# 2DBarcodeScanner.net
KiCad netlist of a schematic drawn in EAGLE
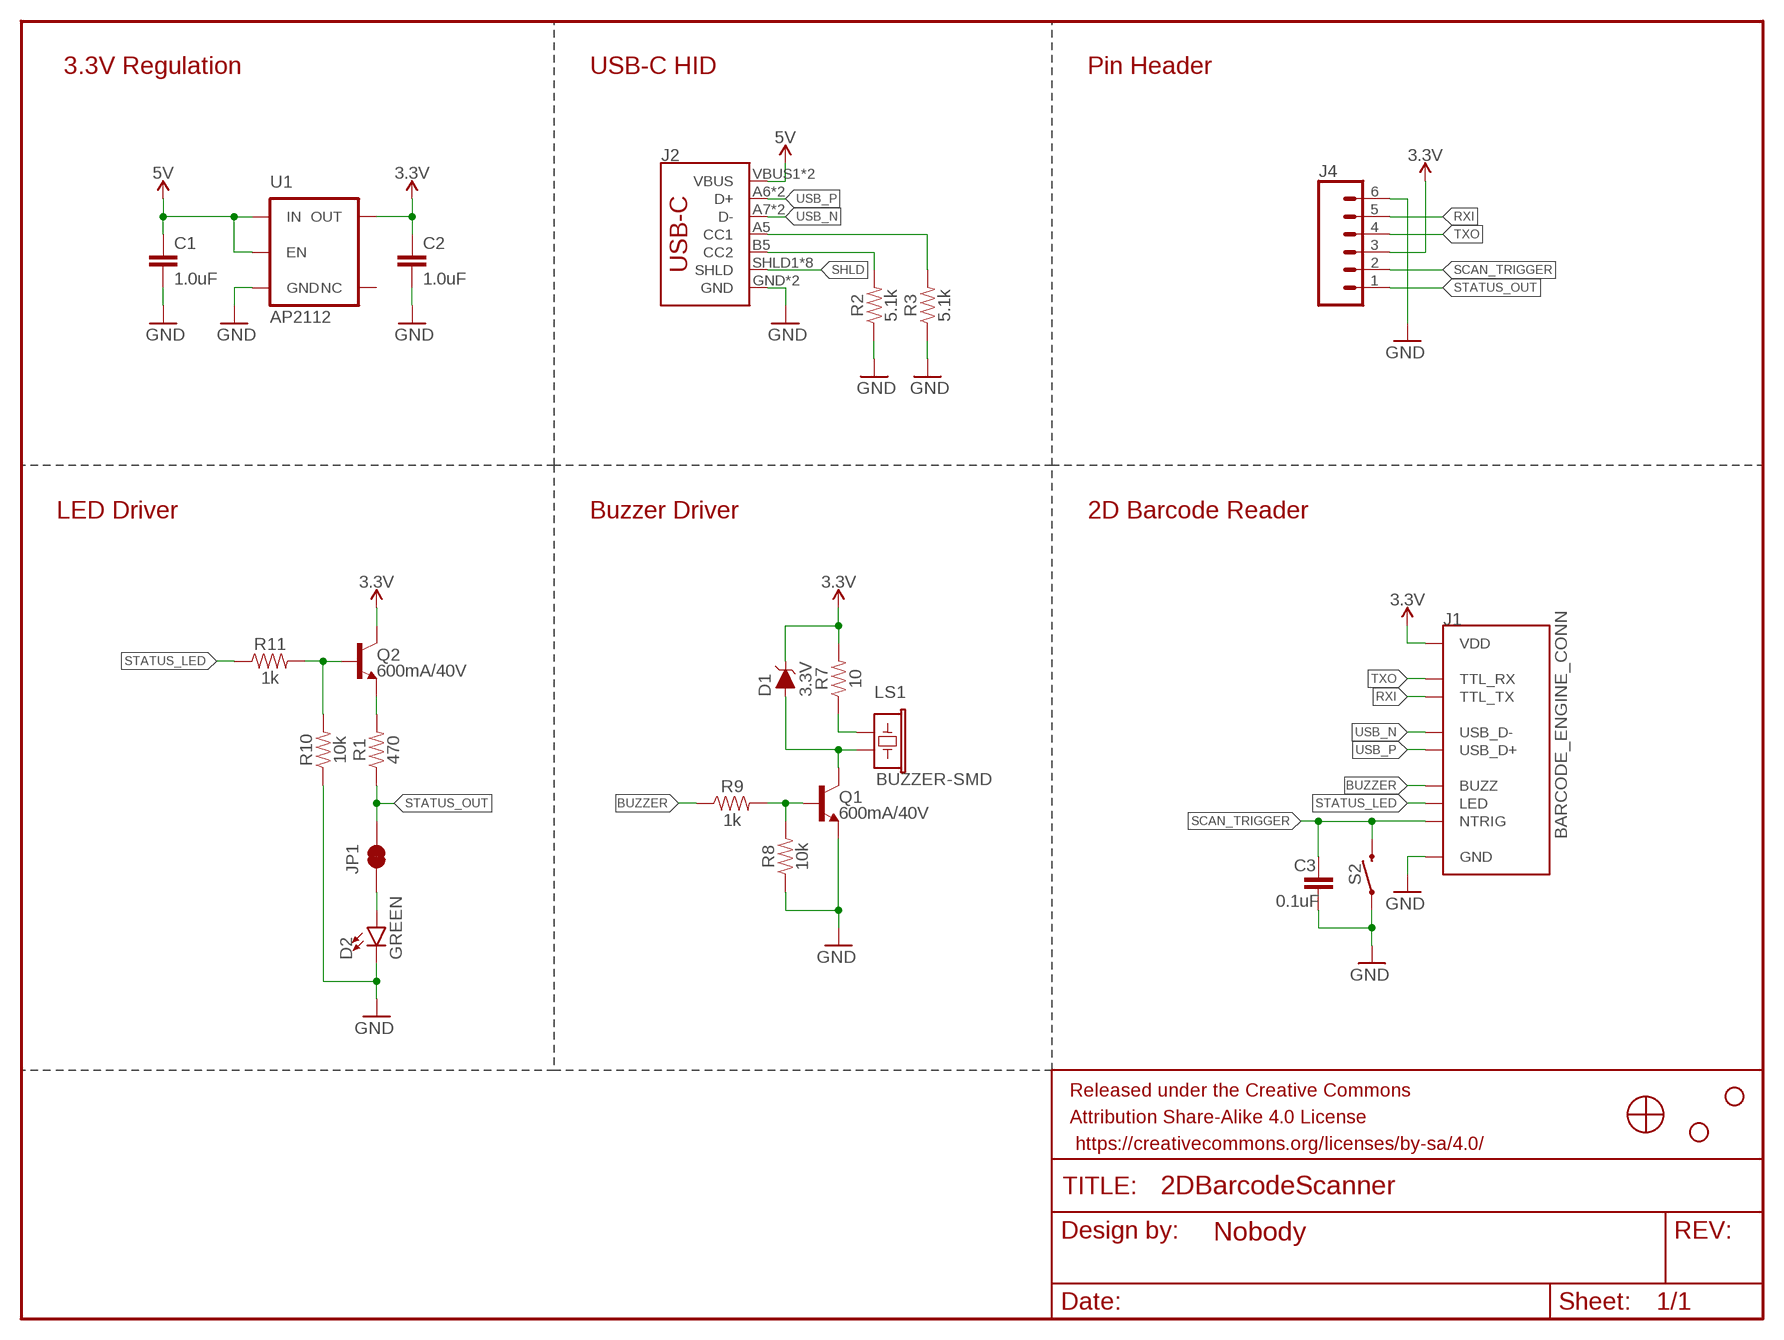
[diagram p0: schematic, sheet 1]

(export (version "E")
  (design (tool "Eeschema 10.0.6"))
  (components
    (comp (ref "C1")
      (value "1.0uF")
      (footprint "eagle-import:0603")
      (libsource (lib "eagle-import") (part "1.0UF-0603-16V-10%"))
    )
    (comp (ref "C2")
      (value "1.0uF")
      (footprint "eagle-import:0603")
      (libsource (lib "eagle-import") (part "1.0UF-0603-16V-10%"))
    )
    (comp (ref "C3")
      (value "0.1uF")
      (footprint "eagle-import:0603")
      (libsource (lib "eagle-import") (part "0.1UF-0603-25V-(+80/-20%)"))
    )
    (comp (ref "D1")
      (value "3.3V")
      (footprint "eagle-import:SOD-323")
      (libsource (lib "eagle-import") (part "DIODE-ZENER-MM3Z3V3T1G"))
    )
    (comp (ref "D2")
      (value "GREEN")
      (footprint "eagle-import:LED-0603")
      (libsource (lib "eagle-import") (part "LED-GREEN0603"))
    )
    (comp (ref "FRAME1")
      (value "FRAME-LETTERNO_PACKAGE")
      (footprint "eagle-import:DUMMY")
      (fields (field (name "DESIGNER") "Nobody"))
      (libsource (lib "eagle-import") (part "FRAME-LETTERNO_PACKAGE"))
    )
    (comp (ref "H2")
      (value "STAND-OFF")
      (footprint "eagle-import:STAND-OFF")
      (libsource (lib "eagle-import") (part "STAND-OFF"))
    )
    (comp (ref "H3")
      (value "STAND-OFF")
      (footprint "eagle-import:STAND-OFF")
      (libsource (lib "eagle-import") (part "STAND-OFF"))
    )
    (comp (ref "J1")
      (value "BARCODE_ENGINE_CONN")
      (footprint "eagle-import:CONN_FPC_BOTTOM_12POS_.5MM_R_A")
      (libsource (lib "eagle-import") (part "BARCODE_ENGINE_CONN"))
    )
    (comp (ref "J2")
      (value "USB_C2-LAYER")
      (footprint "eagle-import:USB-C-16P")
      (libsource (lib "eagle-import") (part "USB_C2-LAYER"))
    )
    (comp (ref "J4")
      (value "CONN_06NO_SILK_FEMALE_PTH")
      (footprint "eagle-import:1X06_NO_SILK")
      (libsource (lib "eagle-import") (part "CONN_06NO_SILK_FEMALE_PTH"))
    )
    (comp (ref "JP1")
      (value "JUMPER-SMT_2_NC_TRACE_SILK")
      (footprint "eagle-import:SMT-JUMPER_2_NC_TRACE_SILK")
      (libsource (lib "eagle-import") (part "JUMPER-SMT_2_NC_TRACE_SILK"))
    )
    (comp (ref "LS1")
      (value "BUZZER-SMD")
      (footprint "eagle-import:BUZZER-CCV")
      (libsource (lib "eagle-import") (part "BUZZER-SMD"))
    )
    (comp (ref "Q1")
      (value "600mA/40V")
      (footprint "eagle-import:SOT23-3")
      (libsource (lib "eagle-import") (part "TRANS_NPN-MMBT2222AL"))
    )
    (comp (ref "Q2")
      (value "600mA/40V")
      (footprint "eagle-import:SOT23-3")
      (libsource (lib "eagle-import") (part "TRANS_NPN-MMBT2222AL"))
    )
    (comp (ref "R1")
      (value "470")
      (footprint "eagle-import:0603")
      (libsource (lib "eagle-import") (part "470OHM-0603-1/10W-1%"))
    )
    (comp (ref "R2")
      (value "5.1k")
      (footprint "eagle-import:0603")
      (libsource (lib "eagle-import") (part "5.1KOHM5.1KOHM-0603-1/10W-1%"))
    )
    (comp (ref "R3")
      (value "5.1k")
      (footprint "eagle-import:0603")
      (libsource (lib "eagle-import") (part "5.1KOHM5.1KOHM-0603-1/10W-1%"))
    )
    (comp (ref "R7")
      (value "10")
      (footprint "eagle-import:0603")
      (libsource (lib "eagle-import") (part "10OHM-0603-1/10W-5%"))
    )
    (comp (ref "R8")
      (value "10k")
      (footprint "eagle-import:0603")
      (libsource (lib "eagle-import") (part "10KOHM-0603-1/10W-1%"))
    )
    (comp (ref "R9")
      (value "1k")
      (footprint "eagle-import:0603")
      (libsource (lib "eagle-import") (part "1KOHM-0603-1/10W-1%"))
    )
    (comp (ref "R10")
      (value "10k")
      (footprint "eagle-import:0603")
      (libsource (lib "eagle-import") (part "10KOHM-0603-1/10W-1%"))
    )
    (comp (ref "R11")
      (value "1k")
      (footprint "eagle-import:0603")
      (libsource (lib "eagle-import") (part "1KOHM-0603-1/10W-1%"))
    )
    (comp (ref "S2")
      (value "MOMENTARY-SWITCH-SPST-SMD-5.2MM-TALL")
      (footprint "eagle-import:TACTILE_SWITCH_SMD_5.2MM")
      (libsource (lib "eagle-import") (part "MOMENTARY-SWITCH-SPST-SMD-5.2MM-TALL"))
    )
    (comp (ref "U$1")
      (value "BARCODE_SCANNER_MOUNT")
      (footprint "eagle-import:BARCODE_SCANNER_MOUNT")
      (libsource (lib "eagle-import") (part "BARCODE_SCANNER_MOUNT"))
    )
    (comp (ref "U1")
      (value "3.3V")
      (footprint "eagle-import:SOT23-5")
      (libsource (lib "eagle-import") (part "V_REG_AP2112K-3.3V"))
    )
  )
  (nets
    (net (code "1") (name "3.3V") (class "Default")
      (node (ref "C2") (pin "1") (pinfunction "1_1") (pintype "passive"))
      (node (ref "D1") (pin "C") (pinfunction "C_C") (pintype "passive"))
      (node (ref "J1") (pin "P$11") (pinfunction "VDD_P$11") (pintype "power_in"))
      (node (ref "J4") (pin "3") (pinfunction "3_3") (pintype "passive"))
      (node (ref "Q2") (pin "3") (pinfunction "C_3") (pintype "passive"))
      (node (ref "R7") (pin "2") (pinfunction "2_2") (pintype "passive"))
      (node (ref "U1") (pin "5") (pinfunction "OUT_5") (pintype "passive"))
    )
    (net (code "2") (name "5V") (class "Default")
      (node (ref "C1") (pin "1") (pinfunction "1_1") (pintype "passive"))
      (node (ref "J2") (pin "VBUS1") (pinfunction "VBUS_VBUS1") (pintype "bidirectional"))
      (node (ref "J2") (pin "VBUS2") (pinfunction "VBUS_VBUS2") (pintype "bidirectional"))
      (node (ref "U1") (pin "1") (pinfunction "IN_1") (pintype "input"))
      (node (ref "U1") (pin "3") (pinfunction "EN_3") (pintype "input"))
    )
    (net (code "3") (name "BUZZER") (class "Default")
      (node (ref "J1") (pin "P$4") (pinfunction "BUZZ_P$4") (pintype "output"))
      (node (ref "R9") (pin "1") (pinfunction "1_1") (pintype "passive"))
    )
    (net (code "4") (name "GND") (class "Default")
      (node (ref "C1") (pin "2") (pinfunction "2_2") (pintype "passive"))
      (node (ref "C2") (pin "2") (pinfunction "2_2") (pintype "passive"))
      (node (ref "C3") (pin "2") (pinfunction "2_2") (pintype "passive"))
      (node (ref "D2") (pin "C") (pinfunction "C_C") (pintype "passive"))
      (node (ref "J1") (pin "P$10") (pinfunction "GND_P$10") (pintype "power_in"))
      (node (ref "J1") (pin "P$13") (pinfunction "GND_P$13") (pintype "power_in"))
      (node (ref "J1") (pin "P$14") (pinfunction "GND_P$14") (pintype "power_in"))
      (node (ref "J2") (pin "GND") (pinfunction "GND_GND") (pintype "bidirectional"))
      (node (ref "J2") (pin "GND2") (pinfunction "GND_GND2") (pintype "bidirectional"))
      (node (ref "J4") (pin "6") (pinfunction "6_6") (pintype "passive"))
      (node (ref "Q1") (pin "2") (pinfunction "E_2") (pintype "passive"))
      (node (ref "R10") (pin "1") (pinfunction "1_1") (pintype "passive"))
      (node (ref "R2") (pin "1") (pinfunction "1_1") (pintype "passive"))
      (node (ref "R3") (pin "1") (pinfunction "1_1") (pintype "passive"))
      (node (ref "R8") (pin "1") (pinfunction "1_1") (pintype "passive"))
      (node (ref "S2") (pin "1") (pinfunction "1_1") (pintype "passive"))
      (node (ref "U1") (pin "2") (pinfunction "GND_2") (pintype "input"))
    )
    (net (code "5") (name "Net-(D2-PadA)") (class "Default")
      (node (ref "D2") (pin "A") (pinfunction "A_A") (pintype "passive"))
      (node (ref "JP1") (pin "1") (pinfunction "1_1") (pintype "passive"))
    )
    (net (code "6") (name "Net-(J2-CC1)") (class "Default")
      (node (ref "J2") (pin "A5") (pinfunction "CC1_A5") (pintype "bidirectional"))
      (node (ref "R3") (pin "2") (pinfunction "2_2") (pintype "passive"))
    )
    (net (code "7") (name "Net-(J2-CC2)") (class "Default")
      (node (ref "J2") (pin "B5") (pinfunction "CC2_B5") (pintype "bidirectional"))
      (node (ref "R2") (pin "2") (pinfunction "2_2") (pintype "passive"))
    )
    (net (code "8") (name "Net-(LS1-1)") (class "Default")
      (node (ref "LS1") (pin "+") (pinfunction "1_+") (pintype "passive"))
      (node (ref "R7") (pin "1") (pinfunction "1_1") (pintype "passive"))
    )
    (net (code "9") (name "Net-(LS1-2)") (class "Default")
      (node (ref "D1") (pin "A") (pinfunction "A_A") (pintype "passive"))
      (node (ref "LS1") (pin "-") (pinfunction "2_-") (pintype "passive"))
      (node (ref "Q1") (pin "3") (pinfunction "C_3") (pintype "passive"))
    )
    (net (code "10") (name "Net-(Q1-B)") (class "Default")
      (node (ref "Q1") (pin "1") (pinfunction "B_1") (pintype "passive"))
      (node (ref "R8") (pin "2") (pinfunction "2_2") (pintype "passive"))
      (node (ref "R9") (pin "2") (pinfunction "2_2") (pintype "passive"))
    )
    (net (code "11") (name "Net-(Q2-B)") (class "Default")
      (node (ref "Q2") (pin "1") (pinfunction "B_1") (pintype "passive"))
      (node (ref "R10") (pin "2") (pinfunction "2_2") (pintype "passive"))
      (node (ref "R11") (pin "2") (pinfunction "2_2") (pintype "passive"))
    )
    (net (code "12") (name "Net-(Q2-E)") (class "Default")
      (node (ref "Q2") (pin "2") (pinfunction "E_2") (pintype "passive"))
      (node (ref "R1") (pin "2") (pinfunction "2_2") (pintype "passive"))
    )
    (net (code "13") (name "RXI") (class "Default")
      (node (ref "J1") (pin "P$8") (pinfunction "TTL_TX_P$8") (pintype "output"))
      (node (ref "J4") (pin "5") (pinfunction "5_5") (pintype "passive"))
    )
    (net (code "14") (name "SCAN_TRIGGER") (class "Default")
      (node (ref "C3") (pin "1") (pinfunction "1_1") (pintype "passive"))
      (node (ref "J1") (pin "P$1") (pinfunction "NTRIG_P$1") (pintype "input"))
      (node (ref "J4") (pin "2") (pinfunction "2_2") (pintype "passive"))
      (node (ref "S2") (pin "3") (pinfunction "2_3") (pintype "passive"))
    )
    (net (code "15") (name "SHLD") (class "Default")
      (node (ref "J2") (pin "SHLD1") (pinfunction "SHLD_SHLD1") (pintype "bidirectional"))
      (node (ref "J2") (pin "SHLD2") (pinfunction "SHLD_SHLD2") (pintype "bidirectional"))
      (node (ref "J2") (pin "SHLD3") (pinfunction "SHLD_SHLD3") (pintype "bidirectional"))
      (node (ref "J2") (pin "SHLD4") (pinfunction "SHLD_SHLD4") (pintype "bidirectional"))
      (node (ref "J2") (pin "SHLD5") (pinfunction "SHLD_SHLD5") (pintype "bidirectional"))
      (node (ref "J2") (pin "SHLD6") (pinfunction "SHLD_SHLD6") (pintype "bidirectional"))
      (node (ref "J2") (pin "SHLD7") (pinfunction "SHLD_SHLD7") (pintype "bidirectional"))
      (node (ref "J2") (pin "SHLD8") (pinfunction "SHLD_SHLD8") (pintype "bidirectional"))
    )
    (net (code "16") (name "STATUS_LED") (class "Default")
      (node (ref "J1") (pin "P$3") (pinfunction "LED_P$3") (pintype "input"))
      (node (ref "R11") (pin "1") (pinfunction "1_1") (pintype "passive"))
    )
    (net (code "17") (name "STATUS_OUT") (class "Default")
      (node (ref "J4") (pin "1") (pinfunction "1_1") (pintype "passive"))
      (node (ref "JP1") (pin "2") (pinfunction "2_2") (pintype "passive"))
      (node (ref "R1") (pin "1") (pinfunction "1_1") (pintype "passive"))
    )
    (net (code "18") (name "TXO") (class "Default")
      (node (ref "J1") (pin "P$9") (pinfunction "TTL_RX_P$9") (pintype "input"))
      (node (ref "J4") (pin "4") (pinfunction "4_4") (pintype "passive"))
    )
    (net (code "19") (name "USB_N") (class "Default")
      (node (ref "J1") (pin "P$7") (pinfunction "USB_D-_P$7") (pintype "bidirectional"))
      (node (ref "J2") (pin "A7") (pinfunction "D-_A7") (pintype "bidirectional"))
      (node (ref "J2") (pin "B7") (pinfunction "D-_B7") (pintype "bidirectional"))
    )
    (net (code "20") (name "USB_P") (class "Default")
      (node (ref "J1") (pin "P$6") (pinfunction "USB_D+_P$6") (pintype "bidirectional"))
      (node (ref "J2") (pin "A6") (pinfunction "D+_A6") (pintype "bidirectional"))
      (node (ref "J2") (pin "B6") (pinfunction "D+_B6") (pintype "bidirectional"))
    )
    (net (code "21") (name "unconnected-(U1-NC-Pad4)") (class "Default")
      (node (ref "U1") (pin "4") (pinfunction "NC_4") (pintype "no_connect"))
    )
  )
)
